# Input_Filtering.net
KiCad netlist of a schematic drawn in Altium Designer
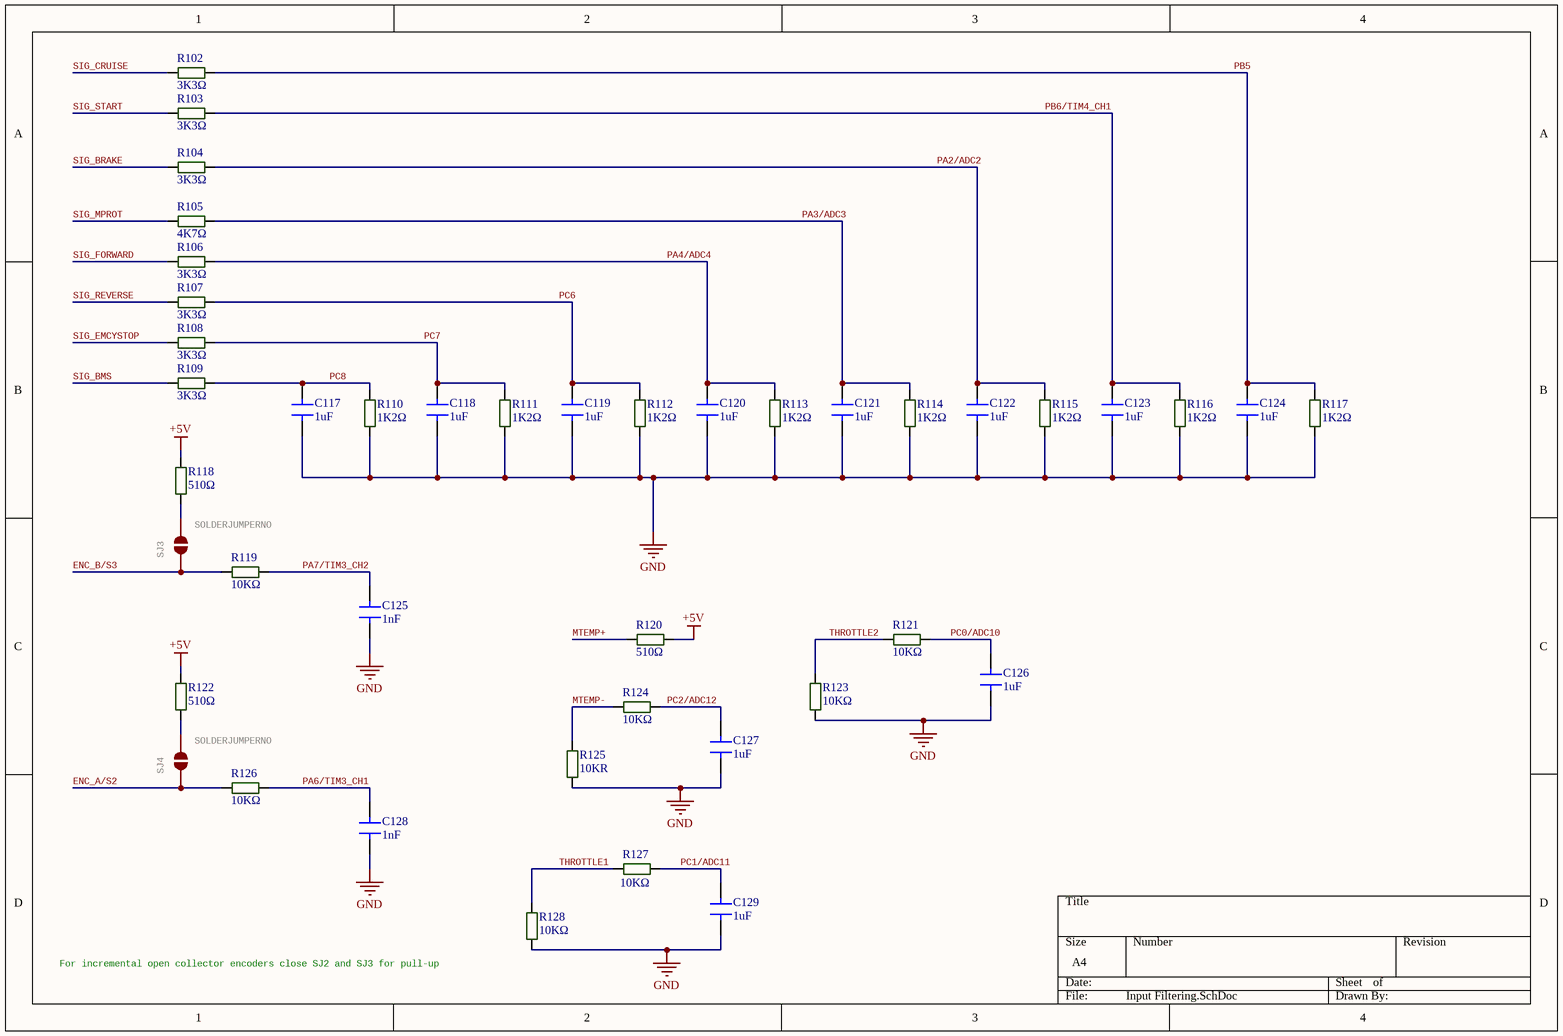
[diagram p0: Input Filtering.SchDoc]

(export (version "E")
  (design (tool "Eeschema 10.0.6"))
  (components
    (comp (ref "C117")
      (value "1uF")
      (footprint "C-0603W")
      (libsource (lib "Gate Driver Board") (part "C-0603"))
    )
    (comp (ref "C118")
      (value "1uF")
      (footprint "C-0603W")
      (libsource (lib "Gate Driver Board") (part "C-0603"))
    )
    (comp (ref "C119")
      (value "1uF")
      (footprint "C-0603W")
      (libsource (lib "Gate Driver Board") (part "C-0603"))
    )
    (comp (ref "C120")
      (value "1uF")
      (footprint "C-0603W")
      (libsource (lib "Gate Driver Board") (part "C-0603"))
    )
    (comp (ref "C121")
      (value "1uF")
      (footprint "C-0603W")
      (libsource (lib "Gate Driver Board") (part "C-0603"))
    )
    (comp (ref "C122")
      (value "1uF")
      (footprint "C-0603W")
      (libsource (lib "Gate Driver Board") (part "C-0603"))
    )
    (comp (ref "C123")
      (value "1uF")
      (footprint "C-0603W")
      (libsource (lib "Gate Driver Board") (part "C-0603"))
    )
    (comp (ref "C124")
      (value "1uF")
      (footprint "C-0603W")
      (libsource (lib "Gate Driver Board") (part "C-0603"))
    )
    (comp (ref "C125")
      (value "1nF")
      (footprint "C-0603W")
      (libsource (lib "Gate Driver Board") (part "C-0603"))
    )
    (comp (ref "C126")
      (value "1uF")
      (footprint "C-0603W")
      (libsource (lib "Gate Driver Board") (part "C-0603"))
    )
    (comp (ref "C127")
      (value "1uF")
      (footprint "C-0603W")
      (libsource (lib "Gate Driver Board") (part "C-0603"))
    )
    (comp (ref "C128")
      (value "1nF")
      (footprint "C-0603W")
      (libsource (lib "Gate Driver Board") (part "C-0603"))
    )
    (comp (ref "C129")
      (value "1uF")
      (footprint "C-0603W")
      (libsource (lib "Gate Driver Board") (part "C-0603"))
    )
    (comp (ref "R102")
      (value "3K3Ω")
      (footprint "R-0603R")
      (libsource (lib "Gate Driver Board") (part "R-0603"))
    )
    (comp (ref "R103")
      (value "3K3Ω")
      (footprint "R-0603R")
      (libsource (lib "Gate Driver Board") (part "R-0603"))
    )
    (comp (ref "R104")
      (value "3K3Ω")
      (footprint "R-0603R")
      (libsource (lib "Gate Driver Board") (part "R-0603"))
    )
    (comp (ref "R105")
      (value "4K7Ω")
      (footprint "R-0603R")
      (libsource (lib "Gate Driver Board") (part "R-0603"))
    )
    (comp (ref "R106")
      (value "3K3Ω")
      (footprint "R-0603R")
      (libsource (lib "Gate Driver Board") (part "R-0603"))
    )
    (comp (ref "R107")
      (value "3K3Ω")
      (footprint "R-0603R")
      (libsource (lib "Gate Driver Board") (part "R-0603"))
    )
    (comp (ref "R108")
      (value "3K3Ω")
      (footprint "R-0603R")
      (libsource (lib "Gate Driver Board") (part "R-0603"))
    )
    (comp (ref "R109")
      (value "3K3Ω")
      (footprint "R-0603R")
      (libsource (lib "Gate Driver Board") (part "R-0603"))
    )
    (comp (ref "R110")
      (value "1K2Ω")
      (footprint "R-0603R")
      (libsource (lib "Gate Driver Board") (part "R-0603"))
    )
    (comp (ref "R111")
      (value "1K2Ω")
      (footprint "R-0603R")
      (libsource (lib "Gate Driver Board") (part "R-0603"))
    )
    (comp (ref "R112")
      (value "1K2Ω")
      (footprint "R-0603R")
      (libsource (lib "Gate Driver Board") (part "R-0603"))
    )
    (comp (ref "R113")
      (value "1K2Ω")
      (footprint "R-0603R")
      (libsource (lib "Gate Driver Board") (part "R-0603"))
    )
    (comp (ref "R114")
      (value "1K2Ω")
      (footprint "R-0603R")
      (libsource (lib "Gate Driver Board") (part "R-0603"))
    )
    (comp (ref "R115")
      (value "1K2Ω")
      (footprint "R-0603R")
      (libsource (lib "Gate Driver Board") (part "R-0603"))
    )
    (comp (ref "R116")
      (value "1K2Ω")
      (footprint "R-0603R")
      (libsource (lib "Gate Driver Board") (part "R-0603"))
    )
    (comp (ref "R117")
      (value "1K2Ω")
      (footprint "R-0603R")
      (libsource (lib "Gate Driver Board") (part "R-0603"))
    )
    (comp (ref "R118")
      (value "510Ω")
      (footprint "R-0603R")
      (libsource (lib "Gate Driver Board") (part "R-0603"))
    )
    (comp (ref "R119")
      (value "10KΩ")
      (footprint "R-0603R")
      (libsource (lib "Gate Driver Board") (part "R-0603"))
    )
    (comp (ref "R120")
      (value "510Ω")
      (footprint "R-0603R")
      (libsource (lib "Gate Driver Board") (part "R-0603"))
    )
    (comp (ref "R121")
      (value "10KΩ")
      (footprint "R-0603R")
      (libsource (lib "Gate Driver Board") (part "R-0603"))
    )
    (comp (ref "R122")
      (value "510Ω")
      (footprint "R-0603R")
      (libsource (lib "Gate Driver Board") (part "R-0603"))
    )
    (comp (ref "R123")
      (value "10KΩ")
      (footprint "R-0603R")
      (libsource (lib "Gate Driver Board") (part "R-0603"))
    )
    (comp (ref "R124")
      (value "10KΩ")
      (footprint "R-0603R")
      (libsource (lib "Gate Driver Board") (part "R-0603"))
    )
    (comp (ref "R125")
      (value "10KR")
      (footprint "R-0603R")
      (libsource (lib "Gate Driver Board") (part "R-0603"))
    )
    (comp (ref "R126")
      (value "10KΩ")
      (footprint "R-0603R")
      (libsource (lib "Gate Driver Board") (part "R-0603"))
    )
    (comp (ref "R127")
      (value "10KΩ")
      (footprint "R-0603R")
      (libsource (lib "Gate Driver Board") (part "R-0603"))
    )
    (comp (ref "R128")
      (value "10KΩ")
      (footprint "R-0603R")
      (libsource (lib "Gate Driver Board") (part "R-0603"))
    )
    (comp (ref "SJ3")
      (value "SOLDERJUMPERNO")
      (footprint "SJ_2S-NO")
      (libsource (lib "Gate Driver Board") (part "SOLDERJUMPERNO"))
    )
    (comp (ref "SJ4")
      (value "SOLDERJUMPERNO")
      (footprint "SJ_2S-NO")
      (libsource (lib "Gate Driver Board") (part "SOLDERJUMPERNO"))
    )
  )
  (nets
    (net (code "1") (name "+5V") (class "Default")
      (node (ref "R118") (pin "2") (pinfunction "2_2") (pintype "passive"))
      (node (ref "R120") (pin "2") (pinfunction "2_2") (pintype "passive"))
      (node (ref "R122") (pin "2") (pinfunction "2_2") (pintype "passive"))
    )
    (net (code "2") (name "/ENC_A{slash}S2") (class "Default")
      (node (ref "R126") (pin "1") (pinfunction "1_1") (pintype "passive"))
      (node (ref "SJ4") (pin "1") (pinfunction "1_1") (pintype "passive"))
    )
    (net (code "3") (name "/ENC_B{slash}S3") (class "Default")
      (node (ref "R119") (pin "1") (pinfunction "1_1") (pintype "passive"))
      (node (ref "SJ3") (pin "1") (pinfunction "1_1") (pintype "passive"))
    )
    (net (code "4") (name "/MTEMP+") (class "Default")
      (node (ref "R120") (pin "1") (pinfunction "1_1") (pintype "passive"))
    )
    (net (code "5") (name "/MTEMP-") (class "Default")
      (node (ref "R124") (pin "1") (pinfunction "1_1") (pintype "passive"))
      (node (ref "R125") (pin "2") (pinfunction "2_2") (pintype "passive"))
    )
    (net (code "6") (name "/PA2{slash}ADC2") (class "Default")
      (node (ref "C122") (pin "2") (pinfunction "2_2") (pintype "passive"))
      (node (ref "R104") (pin "2") (pinfunction "2_2") (pintype "passive"))
      (node (ref "R115") (pin "2") (pinfunction "2_2") (pintype "passive"))
    )
    (net (code "7") (name "/PA3{slash}ADC3") (class "Default")
      (node (ref "C121") (pin "2") (pinfunction "2_2") (pintype "passive"))
      (node (ref "R105") (pin "2") (pinfunction "2_2") (pintype "passive"))
      (node (ref "R114") (pin "2") (pinfunction "2_2") (pintype "passive"))
    )
    (net (code "8") (name "/PA4{slash}ADC4") (class "Default")
      (node (ref "C120") (pin "2") (pinfunction "2_2") (pintype "passive"))
      (node (ref "R106") (pin "2") (pinfunction "2_2") (pintype "passive"))
      (node (ref "R113") (pin "2") (pinfunction "2_2") (pintype "passive"))
    )
    (net (code "9") (name "/PA6{slash}TIM3_CH1") (class "Default")
      (node (ref "C128") (pin "2") (pinfunction "2_2") (pintype "passive"))
      (node (ref "R126") (pin "2") (pinfunction "2_2") (pintype "passive"))
    )
    (net (code "10") (name "/PA7{slash}TIM3_CH2") (class "Default")
      (node (ref "C125") (pin "2") (pinfunction "2_2") (pintype "passive"))
      (node (ref "R119") (pin "2") (pinfunction "2_2") (pintype "passive"))
    )
    (net (code "11") (name "/PB5") (class "Default")
      (node (ref "C124") (pin "2") (pinfunction "2_2") (pintype "passive"))
      (node (ref "R102") (pin "2") (pinfunction "2_2") (pintype "passive"))
      (node (ref "R117") (pin "2") (pinfunction "2_2") (pintype "passive"))
    )
    (net (code "12") (name "/PB6{slash}TIM4_CH1") (class "Default")
      (node (ref "C123") (pin "2") (pinfunction "2_2") (pintype "passive"))
      (node (ref "R103") (pin "2") (pinfunction "2_2") (pintype "passive"))
      (node (ref "R116") (pin "2") (pinfunction "2_2") (pintype "passive"))
    )
    (net (code "13") (name "/PC0{slash}ADC10") (class "Default")
      (node (ref "C126") (pin "2") (pinfunction "2_2") (pintype "passive"))
      (node (ref "R121") (pin "2") (pinfunction "2_2") (pintype "passive"))
    )
    (net (code "14") (name "/PC1{slash}ADC11") (class "Default")
      (node (ref "C129") (pin "2") (pinfunction "2_2") (pintype "passive"))
      (node (ref "R127") (pin "2") (pinfunction "2_2") (pintype "passive"))
    )
    (net (code "15") (name "/PC2{slash}ADC12") (class "Default")
      (node (ref "C127") (pin "2") (pinfunction "2_2") (pintype "passive"))
      (node (ref "R124") (pin "2") (pinfunction "2_2") (pintype "passive"))
    )
    (net (code "16") (name "/PC6") (class "Default")
      (node (ref "C119") (pin "2") (pinfunction "2_2") (pintype "passive"))
      (node (ref "R107") (pin "2") (pinfunction "2_2") (pintype "passive"))
      (node (ref "R112") (pin "2") (pinfunction "2_2") (pintype "passive"))
    )
    (net (code "17") (name "/PC7") (class "Default")
      (node (ref "C118") (pin "2") (pinfunction "2_2") (pintype "passive"))
      (node (ref "R108") (pin "2") (pinfunction "2_2") (pintype "passive"))
      (node (ref "R111") (pin "2") (pinfunction "2_2") (pintype "passive"))
    )
    (net (code "18") (name "/PC8") (class "Default")
      (node (ref "C117") (pin "2") (pinfunction "2_2") (pintype "passive"))
      (node (ref "R109") (pin "2") (pinfunction "2_2") (pintype "passive"))
      (node (ref "R110") (pin "2") (pinfunction "2_2") (pintype "passive"))
    )
    (net (code "19") (name "/SIG_BMS") (class "Default")
      (node (ref "R109") (pin "1") (pinfunction "1_1") (pintype "passive"))
    )
    (net (code "20") (name "/SIG_BRAKE") (class "Default")
      (node (ref "R104") (pin "1") (pinfunction "1_1") (pintype "passive"))
    )
    (net (code "21") (name "/SIG_CRUISE") (class "Default")
      (node (ref "R102") (pin "1") (pinfunction "1_1") (pintype "passive"))
    )
    (net (code "22") (name "/SIG_EMCYSTOP") (class "Default")
      (node (ref "R108") (pin "1") (pinfunction "1_1") (pintype "passive"))
    )
    (net (code "23") (name "/SIG_FORWARD") (class "Default")
      (node (ref "R106") (pin "1") (pinfunction "1_1") (pintype "passive"))
    )
    (net (code "24") (name "/SIG_MPROT") (class "Default")
      (node (ref "R105") (pin "1") (pinfunction "1_1") (pintype "passive"))
    )
    (net (code "25") (name "/SIG_REVERSE") (class "Default")
      (node (ref "R107") (pin "1") (pinfunction "1_1") (pintype "passive"))
    )
    (net (code "26") (name "/SIG_START") (class "Default")
      (node (ref "R103") (pin "1") (pinfunction "1_1") (pintype "passive"))
    )
    (net (code "27") (name "/THROTTLE1") (class "Default")
      (node (ref "R127") (pin "1") (pinfunction "1_1") (pintype "passive"))
      (node (ref "R128") (pin "2") (pinfunction "2_2") (pintype "passive"))
    )
    (net (code "28") (name "/THROTTLE2") (class "Default")
      (node (ref "R121") (pin "1") (pinfunction "1_1") (pintype "passive"))
      (node (ref "R123") (pin "2") (pinfunction "2_2") (pintype "passive"))
    )
    (net (code "29") (name "GND") (class "Default")
      (node (ref "C117") (pin "1") (pinfunction "1_1") (pintype "passive"))
      (node (ref "C118") (pin "1") (pinfunction "1_1") (pintype "passive"))
      (node (ref "C119") (pin "1") (pinfunction "1_1") (pintype "passive"))
      (node (ref "C120") (pin "1") (pinfunction "1_1") (pintype "passive"))
      (node (ref "C121") (pin "1") (pinfunction "1_1") (pintype "passive"))
      (node (ref "C122") (pin "1") (pinfunction "1_1") (pintype "passive"))
      (node (ref "C123") (pin "1") (pinfunction "1_1") (pintype "passive"))
      (node (ref "C124") (pin "1") (pinfunction "1_1") (pintype "passive"))
      (node (ref "C125") (pin "1") (pinfunction "1_1") (pintype "passive"))
      (node (ref "C126") (pin "1") (pinfunction "1_1") (pintype "passive"))
      (node (ref "C127") (pin "1") (pinfunction "1_1") (pintype "passive"))
      (node (ref "C128") (pin "1") (pinfunction "1_1") (pintype "passive"))
      (node (ref "C129") (pin "1") (pinfunction "1_1") (pintype "passive"))
      (node (ref "R110") (pin "1") (pinfunction "1_1") (pintype "passive"))
      (node (ref "R111") (pin "1") (pinfunction "1_1") (pintype "passive"))
      (node (ref "R112") (pin "1") (pinfunction "1_1") (pintype "passive"))
      (node (ref "R113") (pin "1") (pinfunction "1_1") (pintype "passive"))
      (node (ref "R114") (pin "1") (pinfunction "1_1") (pintype "passive"))
      (node (ref "R115") (pin "1") (pinfunction "1_1") (pintype "passive"))
      (node (ref "R116") (pin "1") (pinfunction "1_1") (pintype "passive"))
      (node (ref "R117") (pin "1") (pinfunction "1_1") (pintype "passive"))
      (node (ref "R123") (pin "1") (pinfunction "1_1") (pintype "passive"))
      (node (ref "R125") (pin "1") (pinfunction "1_1") (pintype "passive"))
      (node (ref "R128") (pin "1") (pinfunction "1_1") (pintype "passive"))
    )
    (net (code "30") (name "Net-(R118-Pad1)") (class "Default")
      (node (ref "R118") (pin "1") (pinfunction "1_1") (pintype "passive"))
      (node (ref "SJ3") (pin "2") (pinfunction "2_2") (pintype "passive"))
    )
    (net (code "31") (name "Net-(R122-Pad1)") (class "Default")
      (node (ref "R122") (pin "1") (pinfunction "1_1") (pintype "passive"))
      (node (ref "SJ4") (pin "2") (pinfunction "2_2") (pintype "passive"))
    )
  )
)
